# AUDIO.net
KiCad netlist of a schematic drawn in Altium Designer
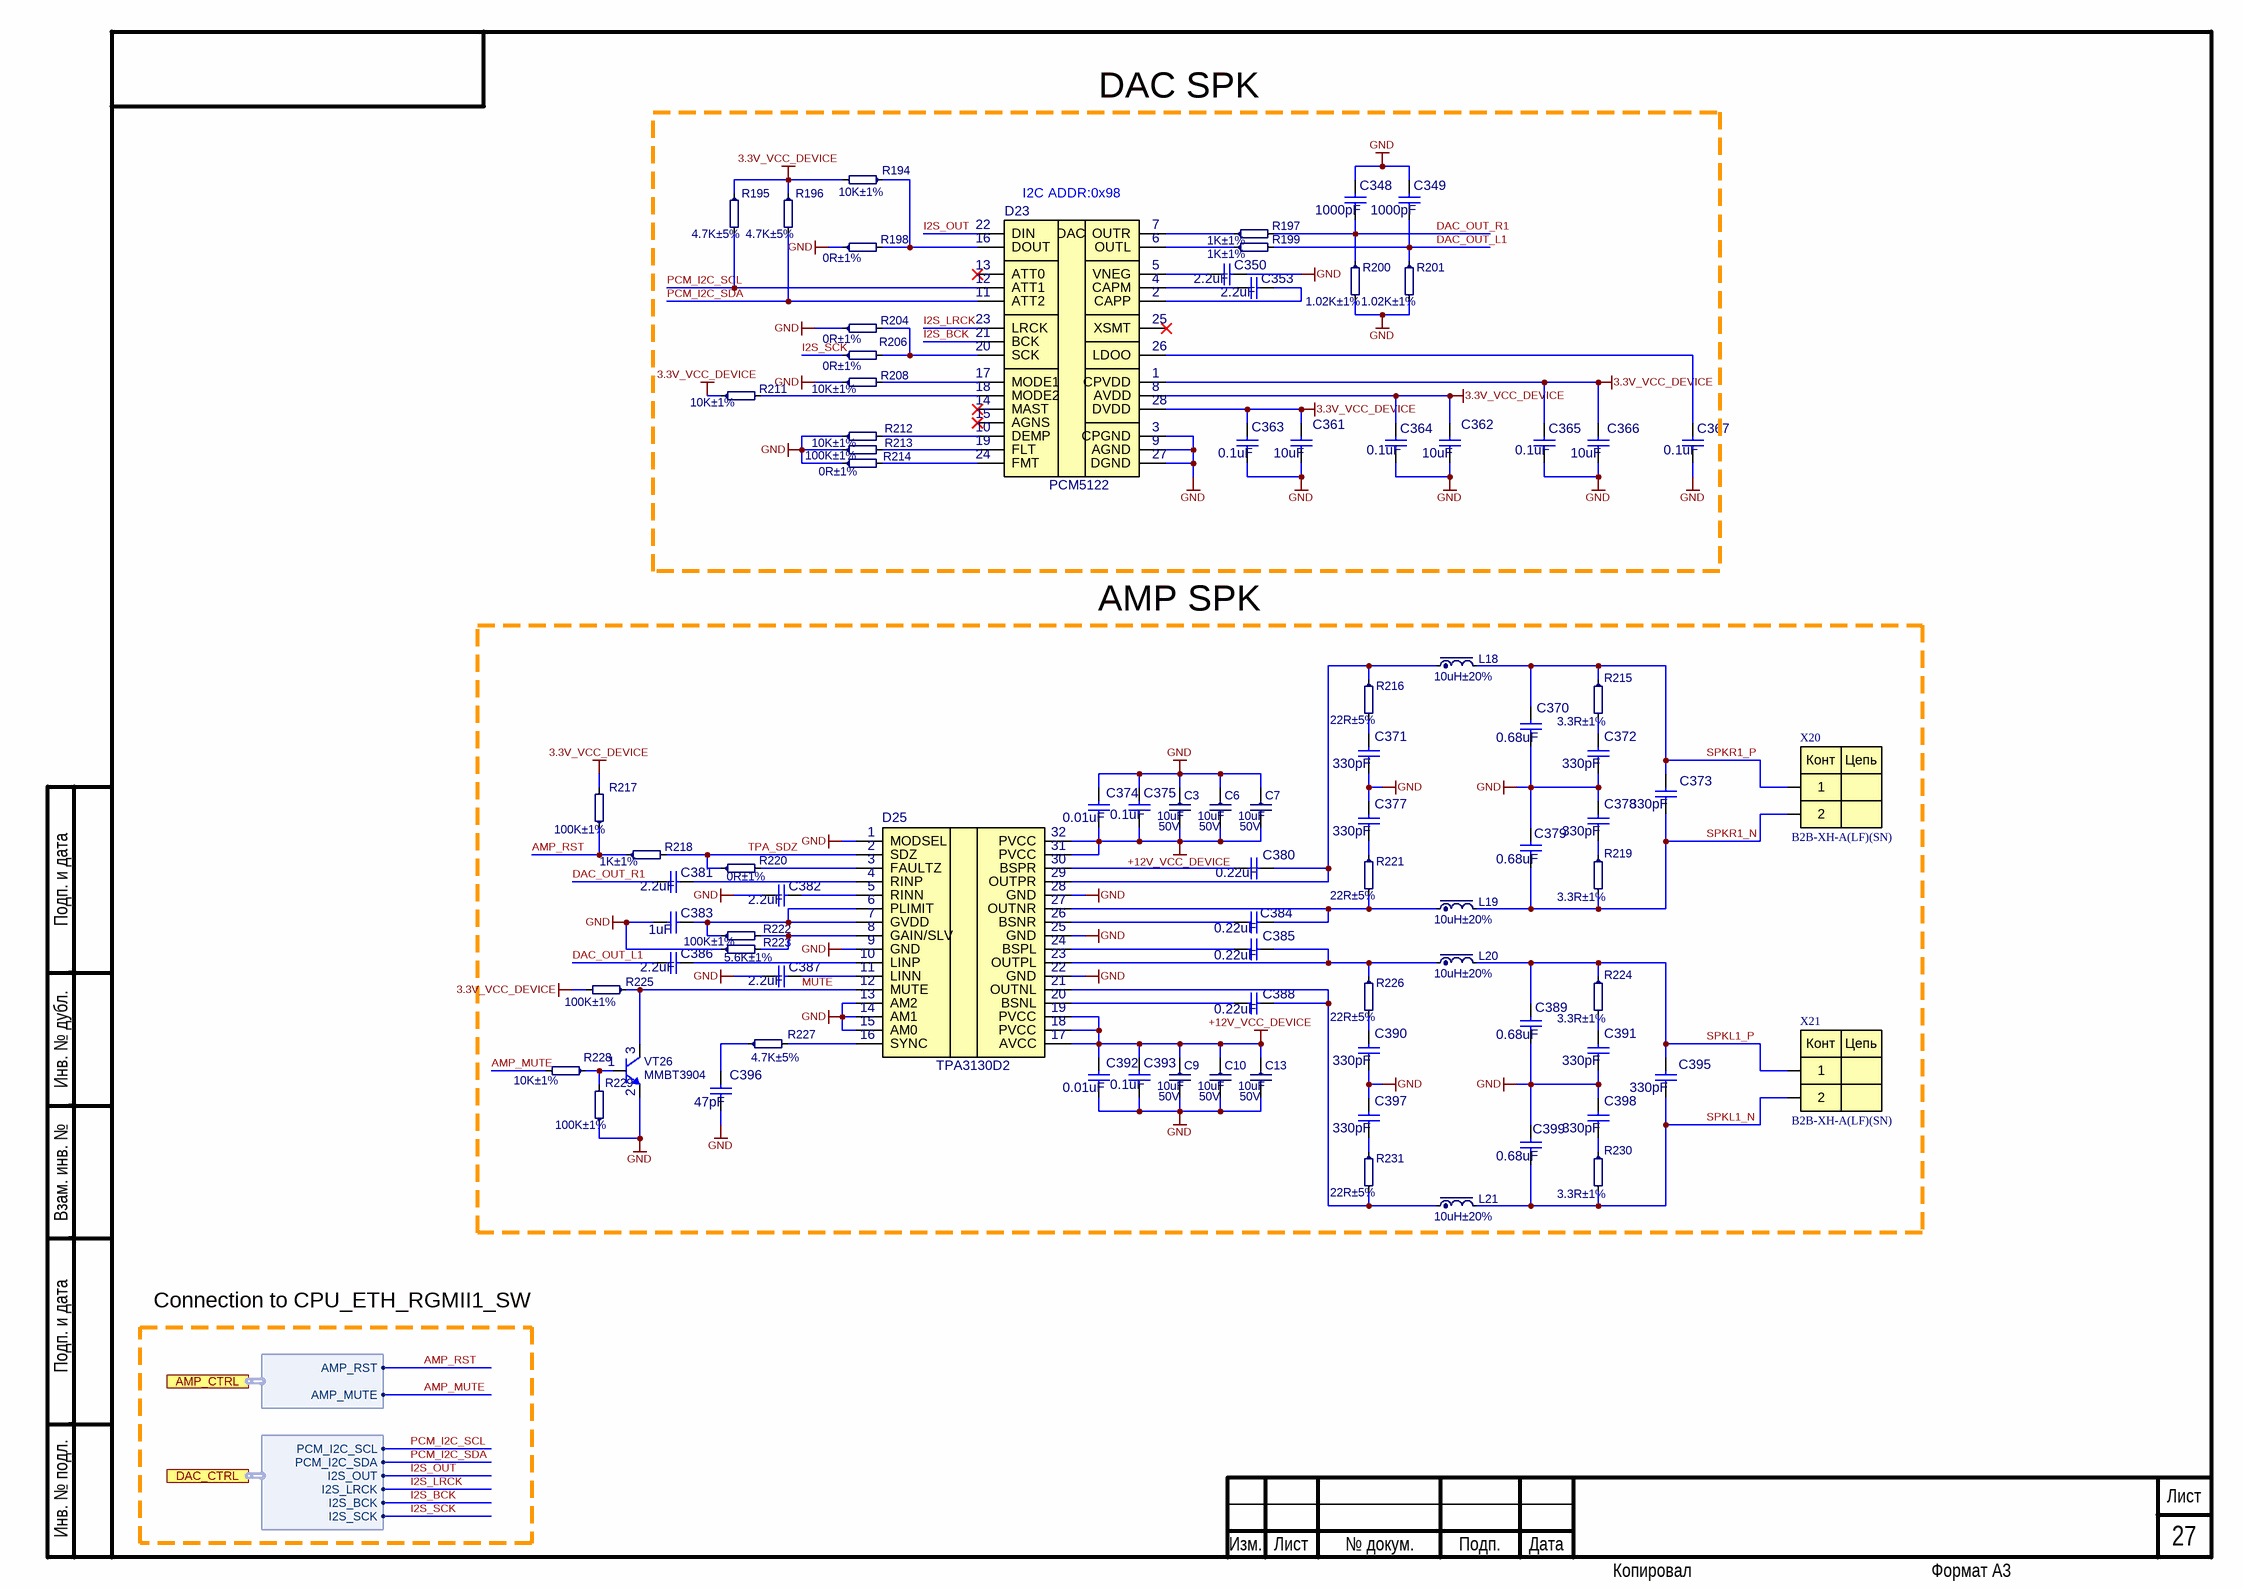
[diagram p0: AUDIO.SchDoc]

(export (version "E")
  (design (tool "Eeschema 10.0.6"))
  (components
    (comp (ref "C3")
      (value "10uF")
      (footprint "C1206")
      (fields
        (field (name "VOLTAGE") "50V")
        (field (name "PART NUMBER") "1206-X5R-50V-010uF±10%")
        (field (name "TOLERANCE") "10%")
        (field (name "MANUFACTURER") "Yageo")
      )
      (libsource (lib "") (part "C_1"))
    )
    (comp (ref "C6")
      (value "10uF")
      (footprint "C1206")
      (fields
        (field (name "VOLTAGE") "50V")
        (field (name "PART NUMBER") "1206-X5R-50V-010uF±10%")
        (field (name "TOLERANCE") "10%")
        (field (name "MANUFACTURER") "Yageo")
      )
      (libsource (lib "") (part "C_1"))
    )
    (comp (ref "C7")
      (value "10uF")
      (footprint "C1206")
      (fields
        (field (name "VOLTAGE") "50V")
        (field (name "PART NUMBER") "1206-X5R-50V-010uF±10%")
        (field (name "TOLERANCE") "10%")
        (field (name "MANUFACTURER") "Yageo")
      )
      (libsource (lib "") (part "C_1"))
    )
    (comp (ref "C9")
      (value "10uF")
      (footprint "C1206")
      (fields
        (field (name "VOLTAGE") "50V")
        (field (name "PART NUMBER") "1206-X5R-50V-010uF±10%")
        (field (name "TOLERANCE") "10%")
        (field (name "MANUFACTURER") "Yageo")
      )
      (libsource (lib "") (part "C_1"))
    )
    (comp (ref "C10")
      (value "10uF")
      (footprint "C1206")
      (fields
        (field (name "VOLTAGE") "50V")
        (field (name "PART NUMBER") "1206-X5R-50V-010uF±10%")
        (field (name "TOLERANCE") "10%")
        (field (name "MANUFACTURER") "Yageo")
      )
      (libsource (lib "") (part "C_1"))
    )
    (comp (ref "C13")
      (value "10uF")
      (footprint "C1206")
      (fields
        (field (name "VOLTAGE") "50V")
        (field (name "PART NUMBER") "1206-X5R-50V-010uF±10%")
        (field (name "TOLERANCE") "10%")
        (field (name "MANUFACTURER") "Yageo")
      )
      (libsource (lib "") (part "C_1"))
    )
    (comp (ref "C348")
      (value "1000pF")
      (footprint "C0402")
      (fields
        (field (name "PART NUMBER") "0402-X7R-50V-1000pF±5%")
        (field (name "VOLTAGE") "50V")
        (field (name "TOLERANCE") "5%")
      )
      (libsource (lib "ATB") (part "C"))
    )
    (comp (ref "C349")
      (value "1000pF")
      (footprint "C0402")
      (fields
        (field (name "PART NUMBER") "0402-X7R-50V-1000pF±5%")
        (field (name "VOLTAGE") "50V")
        (field (name "TOLERANCE") "5%")
      )
      (libsource (lib "ATB") (part "C"))
    )
    (comp (ref "C350")
      (value "2.2uF")
      (footprint "C0402")
      (fields
        (field (name "PART NUMBER") "0402-X5R-16V-2.2uF±10%")
        (field (name "VOLTAGE") "16V")
        (field (name "TOLERANCE") "10%")
      )
      (libsource (lib "ATB") (part "C"))
    )
    (comp (ref "C353")
      (value "2.2uF")
      (footprint "C0402")
      (fields
        (field (name "PART NUMBER") "0402-X5R-16V-2.2uF±10%")
        (field (name "VOLTAGE") "16V")
        (field (name "TOLERANCE") "10%")
      )
      (libsource (lib "ATB") (part "C"))
    )
    (comp (ref "C361")
      (value "10uF")
      (footprint "C0603")
      (fields
        (field (name "PART NUMBER") "0603-X5R-10V-10uF±20%")
        (field (name "VOLTAGE") "10V")
        (field (name "TOLERANCE") "20%")
      )
      (libsource (lib "ATB") (part "C"))
    )
    (comp (ref "C362")
      (value "10uF")
      (footprint "C0603")
      (fields
        (field (name "PART NUMBER") "0603-X5R-10V-10uF±20%")
        (field (name "VOLTAGE") "10V")
        (field (name "TOLERANCE") "20%")
      )
      (libsource (lib "ATB") (part "C"))
    )
    (comp (ref "C363")
      (value "0.1uF")
      (footprint "C0402")
      (fields
        (field (name "PART NUMBER") "0402-X5R-50V-0.1uF±10%")
        (field (name "VOLTAGE") "50V")
        (field (name "TOLERANCE") "10%")
      )
      (libsource (lib "ATB") (part "C"))
    )
    (comp (ref "C364")
      (value "0.1uF")
      (footprint "C0402")
      (fields
        (field (name "PART NUMBER") "0402-X5R-50V-0.1uF±10%")
        (field (name "VOLTAGE") "50V")
        (field (name "TOLERANCE") "10%")
      )
      (libsource (lib "ATB") (part "C"))
    )
    (comp (ref "C365")
      (value "0.1uF")
      (footprint "C0402")
      (fields
        (field (name "PART NUMBER") "0402-X5R-50V-0.1uF±10%")
        (field (name "VOLTAGE") "50V")
        (field (name "TOLERANCE") "10%")
      )
      (libsource (lib "ATB") (part "C"))
    )
    (comp (ref "C366")
      (value "10uF")
      (footprint "C0603")
      (fields
        (field (name "PART NUMBER") "0603-X5R-10V-10uF±20%")
        (field (name "VOLTAGE") "10V")
        (field (name "TOLERANCE") "20%")
      )
      (libsource (lib "ATB") (part "C"))
    )
    (comp (ref "C367")
      (value "0.1uF")
      (footprint "C0402")
      (fields
        (field (name "PART NUMBER") "0402-X5R-50V-0.1uF±10%")
        (field (name "VOLTAGE") "50V")
        (field (name "TOLERANCE") "10%")
      )
      (libsource (lib "ATB") (part "C"))
    )
    (comp (ref "C370")
      (value "0.68uF")
      (footprint "C0603")
      (fields
        (field (name "PART NUMBER") "0603-X7R-25V-0.68uF±10%")
        (field (name "VOLTAGE") "25V")
        (field (name "TOLERANCE") "10%")
      )
      (libsource (lib "ATB") (part "C"))
    )
    (comp (ref "C371")
      (value "330pF")
      (footprint "C0603")
      (fields
        (field (name "PART NUMBER") "0603-NP0-50V-330pF±5%")
        (field (name "VOLTAGE") "50V")
        (field (name "TOLERANCE") "5%")
      )
      (libsource (lib "ATB") (part "C"))
    )
    (comp (ref "C372")
      (value "330pF")
      (footprint "C0603")
      (fields
        (field (name "PART NUMBER") "0603-NP0-50V-330pF±5%")
        (field (name "VOLTAGE") "50V")
        (field (name "TOLERANCE") "5%")
      )
      (libsource (lib "ATB") (part "C"))
    )
    (comp (ref "C373")
      (value "330pF")
      (footprint "C0603")
      (fields
        (field (name "PART NUMBER") "0603-NP0-50V-330pF±5%")
        (field (name "VOLTAGE") "50V")
        (field (name "TOLERANCE") "5%")
      )
      (libsource (lib "ATB") (part "C"))
    )
    (comp (ref "C374")
      (value "0.01uF")
      (footprint "C0402")
      (fields
        (field (name "PART NUMBER") "0402-X7R-50V-0.01uF±10%")
        (field (name "VOLTAGE") "50V")
        (field (name "TOLERANCE") "10%")
      )
      (libsource (lib "ATB") (part "C"))
    )
    (comp (ref "C375")
      (value "0.1uF")
      (footprint "C0402")
      (fields
        (field (name "PART NUMBER") "0402-X5R-50V-0.1uF±10%")
        (field (name "VOLTAGE") "50V")
        (field (name "TOLERANCE") "10%")
      )
      (libsource (lib "ATB") (part "C"))
    )
    (comp (ref "C377")
      (value "330pF")
      (footprint "C0603")
      (fields
        (field (name "PART NUMBER") "0603-NP0-50V-330pF±5%")
        (field (name "VOLTAGE") "50V")
        (field (name "TOLERANCE") "5%")
      )
      (libsource (lib "ATB") (part "C"))
    )
    (comp (ref "C378")
      (value "330pF")
      (footprint "C0603")
      (fields
        (field (name "PART NUMBER") "0603-NP0-50V-330pF±5%")
        (field (name "VOLTAGE") "50V")
        (field (name "TOLERANCE") "5%")
      )
      (libsource (lib "ATB") (part "C"))
    )
    (comp (ref "C379")
      (value "0.68uF")
      (footprint "C0603")
      (fields
        (field (name "PART NUMBER") "0603-X7R-25V-0.68uF±10%")
        (field (name "VOLTAGE") "25V")
        (field (name "TOLERANCE") "10%")
      )
      (libsource (lib "ATB") (part "C"))
    )
    (comp (ref "C380")
      (value "0.22uF")
      (footprint "C0603")
      (fields
        (field (name "PART NUMBER") "0603-X5R-50V-0.22uF±10%")
        (field (name "VOLTAGE") "50V")
        (field (name "TOLERANCE") "10%")
      )
      (libsource (lib "ATB") (part "C"))
    )
    (comp (ref "C381")
      (value "2.2uF")
      (footprint "C0402")
      (fields
        (field (name "PART NUMBER") "0402-X5R-16V-2.2uF±10%")
        (field (name "VOLTAGE") "16V")
        (field (name "TOLERANCE") "10%")
      )
      (libsource (lib "ATB") (part "C"))
    )
    (comp (ref "C382")
      (value "2.2uF")
      (footprint "C0402")
      (fields
        (field (name "PART NUMBER") "0402-X5R-16V-2.2uF±10%")
        (field (name "VOLTAGE") "16V")
        (field (name "TOLERANCE") "10%")
      )
      (libsource (lib "ATB") (part "C"))
    )
    (comp (ref "C383")
      (value "1uF")
      (footprint "C0402")
      (fields
        (field (name "PART NUMBER") "0402-X5R-10V-1uF±10%")
        (field (name "VOLTAGE") "10V")
        (field (name "TOLERANCE") "10%")
      )
      (libsource (lib "ATB") (part "C"))
    )
    (comp (ref "C384")
      (value "0.22uF")
      (footprint "C0603")
      (fields
        (field (name "PART NUMBER") "0603-X5R-50V-0.22uF±10%")
        (field (name "VOLTAGE") "50V")
        (field (name "TOLERANCE") "10%")
      )
      (libsource (lib "ATB") (part "C"))
    )
    (comp (ref "C385")
      (value "0.22uF")
      (footprint "C0603")
      (fields
        (field (name "PART NUMBER") "0603-X5R-50V-0.22uF±10%")
        (field (name "VOLTAGE") "50V")
        (field (name "TOLERANCE") "10%")
      )
      (libsource (lib "ATB") (part "C"))
    )
    (comp (ref "C386")
      (value "2.2uF")
      (footprint "C0402")
      (fields
        (field (name "PART NUMBER") "0402-X5R-16V-2.2uF±10%")
        (field (name "VOLTAGE") "16V")
        (field (name "TOLERANCE") "10%")
      )
      (libsource (lib "ATB") (part "C"))
    )
    (comp (ref "C387")
      (value "2.2uF")
      (footprint "C0402")
      (fields
        (field (name "PART NUMBER") "0402-X5R-16V-2.2uF±10%")
        (field (name "VOLTAGE") "16V")
        (field (name "TOLERANCE") "10%")
      )
      (libsource (lib "ATB") (part "C"))
    )
    (comp (ref "C388")
      (value "0.22uF")
      (footprint "C0603")
      (fields
        (field (name "PART NUMBER") "0603-X5R-50V-0.22uF±10%")
        (field (name "VOLTAGE") "50V")
        (field (name "TOLERANCE") "10%")
      )
      (libsource (lib "ATB") (part "C"))
    )
    (comp (ref "C389")
      (value "0.68uF")
      (footprint "C0603")
      (fields
        (field (name "PART NUMBER") "0603-X7R-25V-0.68uF±10%")
        (field (name "VOLTAGE") "25V")
        (field (name "TOLERANCE") "10%")
      )
      (libsource (lib "ATB") (part "C"))
    )
    (comp (ref "C390")
      (value "330pF")
      (footprint "C0603")
      (fields
        (field (name "PART NUMBER") "0603-NP0-50V-330pF±5%")
        (field (name "VOLTAGE") "50V")
        (field (name "TOLERANCE") "5%")
      )
      (libsource (lib "ATB") (part "C"))
    )
    (comp (ref "C391")
      (value "330pF")
      (footprint "C0603")
      (fields
        (field (name "PART NUMBER") "0603-NP0-50V-330pF±5%")
        (field (name "VOLTAGE") "50V")
        (field (name "TOLERANCE") "5%")
      )
      (libsource (lib "ATB") (part "C"))
    )
    (comp (ref "C392")
      (value "0.01uF")
      (footprint "C0402")
      (fields
        (field (name "PART NUMBER") "0402-X7R-50V-0.01uF±10%")
        (field (name "VOLTAGE") "50V")
        (field (name "TOLERANCE") "10%")
      )
      (libsource (lib "ATB") (part "C"))
    )
    (comp (ref "C393")
      (value "0.1uF")
      (footprint "C0402")
      (fields
        (field (name "PART NUMBER") "0402-X5R-50V-0.1uF±10%")
        (field (name "VOLTAGE") "50V")
        (field (name "TOLERANCE") "10%")
      )
      (libsource (lib "ATB") (part "C"))
    )
    (comp (ref "C395")
      (value "330pF")
      (footprint "C0603")
      (fields
        (field (name "PART NUMBER") "0603-NP0-50V-330pF±5%")
        (field (name "VOLTAGE") "50V")
        (field (name "TOLERANCE") "5%")
      )
      (libsource (lib "ATB") (part "C"))
    )
    (comp (ref "C396")
      (value "47pF")
      (footprint "C0402")
      (fields
        (field (name "PART NUMBER") "0402-NP0-50V-047pF±5%")
        (field (name "VOLTAGE") "50V")
        (field (name "TOLERANCE") "5%")
      )
      (libsource (lib "ATB") (part "C"))
    )
    (comp (ref "C397")
      (value "330pF")
      (footprint "C0603")
      (fields
        (field (name "PART NUMBER") "0603-NP0-50V-330pF±5%")
        (field (name "VOLTAGE") "50V")
        (field (name "TOLERANCE") "5%")
      )
      (libsource (lib "ATB") (part "C"))
    )
    (comp (ref "C398")
      (value "330pF")
      (footprint "C0603")
      (fields
        (field (name "PART NUMBER") "0603-NP0-50V-330pF±5%")
        (field (name "VOLTAGE") "50V")
        (field (name "TOLERANCE") "5%")
      )
      (libsource (lib "ATB") (part "C"))
    )
    (comp (ref "C399")
      (value "0.68uF")
      (footprint "C0603")
      (fields
        (field (name "PART NUMBER") "0603-X7R-25V-0.68uF±10%")
        (field (name "VOLTAGE") "25V")
        (field (name "TOLERANCE") "10%")
      )
      (libsource (lib "ATB") (part "C"))
    )
    (comp (ref "D23")
      (value "PCM5122")
      (footprint "TSSOP65-28")
      (description "2V RMS DIRECTPATH 106dB Audio Stereo DAC with PCM interface and fixed Audio processing")
      (fields (field (name "MANUFACTURER") "Texas Instruments"))
      (libsource (lib "ATB") (part "PCM5121_HM"))
    )
    (comp (ref "D25")
      (value "TPA3130D2")
      (footprint "TSOP65P810X115-32M")
      (description "TPA3130D2 Evaluation Module")
      (fields (field (name "MANUFACTURER") "Texas Instruments"))
      (libsource (lib "ATB") (part "TPA3116D2"))
    )
    (comp (ref "L18")
      (value "10uH±20%")
      (footprint "MWSA0605S")
      (description "4.4A 10uH ±20% 4.5A SMD 7x6.6mm Power Inductor")
      (fields (field (name "PART NUMBER") "MWSA0605S-100MT") (field (name "TOLERANCE") "20%"))
      (libsource (lib "ATB") (part "L"))
    )
    (comp (ref "L19")
      (value "10uH±20%")
      (footprint "MWSA0605S")
      (description "4.4A 10uH ±20% 4.5A SMD 7x6.6mm Power Inductor")
      (fields (field (name "PART NUMBER") "MWSA0605S-100MT") (field (name "TOLERANCE") "20%"))
      (libsource (lib "ATB") (part "L"))
    )
    (comp (ref "L20")
      (value "10uH±20%")
      (footprint "MWSA0605S")
      (description "4.4A 10uH ±20% 4.5A SMD 7x6.6mm Power Inductor")
      (fields (field (name "PART NUMBER") "MWSA0605S-100MT") (field (name "TOLERANCE") "20%"))
      (libsource (lib "ATB") (part "L"))
    )
    (comp (ref "L21")
      (value "10uH±20%")
      (footprint "MWSA0605S")
      (description "4.4A 10uH ±20% 4.5A SMD 7x6.6mm Power Inductor")
      (fields (field (name "PART NUMBER") "MWSA0605S-100MT") (field (name "TOLERANCE") "20%"))
      (libsource (lib "ATB") (part "L"))
    )
    (comp (ref "R194")
      (value "10K±1%")
      (footprint "R0402")
      (description "Chip Resistor 0402 10kΩ ±1% 50V ±100ppm/℃ Thick Film")
      (fields (field (name "PART NUMBER") "0402-0.0625W-10K-100ppm±1%") (field (name "TOLERANCE") "1%"))
      (libsource (lib "ATB") (part "R"))
    )
    (comp (ref "R195")
      (value "4.7K±5%")
      (footprint "R0402")
      (fields
        (field (name "PART NUMBER") "0402-0.0625W-4.7K-100ppm±5%")
        (field (name "TOLERANCE") "5%")
        (field (name "MANUFACTURER") "Yageo")
      )
      (libsource (lib "ATB") (part "R"))
    )
    (comp (ref "R196")
      (value "4.7K±5%")
      (footprint "R0402")
      (fields
        (field (name "PART NUMBER") "0402-0.0625W-4.7K-100ppm±5%")
        (field (name "TOLERANCE") "5%")
        (field (name "MANUFACTURER") "Yageo")
      )
      (libsource (lib "ATB") (part "R"))
    )
    (comp (ref "R197")
      (value "1K±1%")
      (footprint "R0402")
      (fields
        (field (name "PART NUMBER") "0402-0.0625W-1K-100ppm±1%")
        (field (name "TOLERANCE") "1%")
        (field (name "MANUFACTURER") "Yageo")
      )
      (libsource (lib "ATB") (part "R"))
    )
    (comp (ref "R198")
      (value "0R±1%")
      (footprint "R0402")
      (description "Chip Resistor 0402 0Ω ±1% 50V ±100ppm/℃ Thick Film")
      (fields (field (name "PART NUMBER") "0402-0.0625W-0R-100ppm±1%") (field (name "TOLERANCE") "1%"))
      (libsource (lib "ATB") (part "R"))
    )
    (comp (ref "R199")
      (value "1K±1%")
      (footprint "R0402")
      (fields
        (field (name "PART NUMBER") "0402-0.0625W-1K-100ppm±1%")
        (field (name "TOLERANCE") "1%")
        (field (name "MANUFACTURER") "Yageo")
      )
      (libsource (lib "ATB") (part "R"))
    )
    (comp (ref "R200")
      (value "1.02K±1%")
      (footprint "R0402")
      (fields
        (field (name "PART NUMBER") "0402-0.0625W-1.02K-100ppm±1%")
        (field (name "TOLERANCE") "1%")
        (field (name "MANUFACTURER") "Yageo")
      )
      (libsource (lib "ATB") (part "R"))
    )
    (comp (ref "R201")
      (value "1.02K±1%")
      (footprint "R0402")
      (fields
        (field (name "PART NUMBER") "0402-0.0625W-1.02K-100ppm±1%")
        (field (name "TOLERANCE") "1%")
        (field (name "MANUFACTURER") "Yageo")
      )
      (libsource (lib "ATB") (part "R"))
    )
    (comp (ref "R204")
      (value "0R±1%")
      (footprint "R0402")
      (description "Chip Resistor 0402 0Ω ±1% 50V ±100ppm/℃ Thick Film")
      (fields (field (name "PART NUMBER") "0402-0.0625W-0R-100ppm±1%") (field (name "TOLERANCE") "1%"))
      (libsource (lib "ATB") (part "R"))
    )
    (comp (ref "R206")
      (value "0R±1%")
      (footprint "R0402")
      (description "Chip Resistor 0402 0Ω ±1% 50V ±100ppm/℃ Thick Film")
      (fields (field (name "PART NUMBER") "0402-0.0625W-0R-100ppm±1%") (field (name "TOLERANCE") "1%"))
      (libsource (lib "ATB") (part "R"))
    )
    (comp (ref "R208")
      (value "10K±1%")
      (footprint "R0402")
      (description "Chip Resistor 0402 10kΩ ±1% 50V ±100ppm/℃ Thick Film")
      (fields (field (name "PART NUMBER") "0402-0.0625W-10K-100ppm±1%") (field (name "TOLERANCE") "1%"))
      (libsource (lib "ATB") (part "R"))
    )
    (comp (ref "R211")
      (value "10K±1%")
      (footprint "R0402")
      (description "Chip Resistor 0402 10kΩ ±1% 50V ±100ppm/℃ Thick Film")
      (fields (field (name "PART NUMBER") "0402-0.0625W-10K-100ppm±1%") (field (name "TOLERANCE") "1%"))
      (libsource (lib "ATB") (part "R"))
    )
    (comp (ref "R212")
      (value "10K±1%")
      (footprint "R0402")
      (description "Chip Resistor 0402 10kΩ ±1% 50V ±100ppm/℃ Thick Film")
      (fields (field (name "PART NUMBER") "0402-0.0625W-10K-100ppm±1%") (field (name "TOLERANCE") "1%"))
      (libsource (lib "ATB") (part "R"))
    )
    (comp (ref "R213")
      (value "100K±1%")
      (footprint "R0402")
      (description "Chip Resistor 0402 100kΩ ±1% 50V ±100ppm/℃ Thick Film")
      (fields (field (name "PART NUMBER") "0402-0.0625W-100K-100ppm±1%") (field (name "TOLERANCE") "1%"))
      (libsource (lib "ATB") (part "R"))
    )
    (comp (ref "R214")
      (value "0R±1%")
      (footprint "R0402")
      (description "Chip Resistor 0402 0Ω ±1% 50V ±100ppm/℃ Thick Film")
      (fields (field (name "PART NUMBER") "0402-0.0625W-0R-100ppm±1%") (field (name "TOLERANCE") "1%"))
      (libsource (lib "ATB") (part "R"))
    )
    (comp (ref "R215")
      (value "3.3R±1%")
      (footprint "R0603")
      (fields
        (field (name "PART NUMBER") "0603-0.1W-3.3R-200ppm±1%")
        (field (name "TOLERANCE") "1%")
        (field (name "MANUFACTURER") "Yageo")
      )
      (libsource (lib "ATB") (part "R"))
    )
    (comp (ref "R216")
      (value "22R±5%")
      (footprint "R0603")
      (fields
        (field (name "PART NUMBER") "0603-0.1W-22R-100ppm±5%")
        (field (name "TOLERANCE") "5%")
        (field (name "MANUFACTURER") "Yageo")
      )
      (libsource (lib "ATB") (part "R"))
    )
    (comp (ref "R217")
      (value "100K±1%")
      (footprint "R0402")
      (description "Chip Resistor 0402 100kΩ ±1% 50V ±100ppm/℃ Thick Film")
      (fields (field (name "PART NUMBER") "0402-0.0625W-100K-100ppm±1%") (field (name "TOLERANCE") "1%"))
      (libsource (lib "ATB") (part "R"))
    )
    (comp (ref "R218")
      (value "1K±1%")
      (footprint "R0402")
      (fields
        (field (name "PART NUMBER") "0402-0.0625W-1K-100ppm±1%")
        (field (name "TOLERANCE") "1%")
        (field (name "MANUFACTURER") "Yageo")
      )
      (libsource (lib "ATB") (part "R"))
    )
    (comp (ref "R219")
      (value "3.3R±1%")
      (footprint "R0603")
      (fields
        (field (name "PART NUMBER") "0603-0.1W-3.3R-200ppm±1%")
        (field (name "TOLERANCE") "1%")
        (field (name "MANUFACTURER") "Yageo")
      )
      (libsource (lib "ATB") (part "R"))
    )
    (comp (ref "R220")
      (value "0R±1%")
      (footprint "R0402")
      (description "Chip Resistor 0402 0Ω ±1% 50V ±100ppm/℃ Thick Film")
      (fields (field (name "PART NUMBER") "0402-0.0625W-0R-100ppm±1%") (field (name "TOLERANCE") "1%"))
      (libsource (lib "ATB") (part "R"))
    )
    (comp (ref "R221")
      (value "22R±5%")
      (footprint "R0603")
      (fields
        (field (name "PART NUMBER") "0603-0.1W-22R-100ppm±5%")
        (field (name "TOLERANCE") "5%")
        (field (name "MANUFACTURER") "Yageo")
      )
      (libsource (lib "ATB") (part "R"))
    )
    (comp (ref "R222")
      (value "100K±1%")
      (footprint "R0402")
      (description "Chip Resistor 0402 100kΩ ±1% 50V ±100ppm/℃ Thick Film")
      (fields (field (name "PART NUMBER") "0402-0.0625W-100K-100ppm±1%") (field (name "TOLERANCE") "1%"))
      (libsource (lib "ATB") (part "R"))
    )
    (comp (ref "R223")
      (value "5.6K±1%")
      (footprint "R0402")
      (fields
        (field (name "PART NUMBER") "0402-0.0625W-5.6K-100ppm±1%")
        (field (name "TOLERANCE") "1%")
        (field (name "MANUFACTURER") "Yageo")
      )
      (libsource (lib "ATB") (part "R"))
    )
    (comp (ref "R224")
      (value "3.3R±1%")
      (footprint "R0603")
      (fields
        (field (name "PART NUMBER") "0603-0.1W-3.3R-200ppm±1%")
        (field (name "TOLERANCE") "1%")
        (field (name "MANUFACTURER") "Yageo")
      )
      (libsource (lib "ATB") (part "R"))
    )
    (comp (ref "R225")
      (value "100K±1%")
      (footprint "R0402")
      (description "Chip Resistor 0402 100kΩ ±1% 50V ±100ppm/℃ Thick Film")
      (fields (field (name "PART NUMBER") "0402-0.0625W-100K-100ppm±1%") (field (name "TOLERANCE") "1%"))
      (libsource (lib "ATB") (part "R"))
    )
    (comp (ref "R226")
      (value "22R±5%")
      (footprint "R0603")
      (fields
        (field (name "PART NUMBER") "0603-0.1W-22R-100ppm±5%")
        (field (name "TOLERANCE") "5%")
        (field (name "MANUFACTURER") "Yageo")
      )
      (libsource (lib "ATB") (part "R"))
    )
    (comp (ref "R227")
      (value "4.7K±5%")
      (footprint "R0402")
      (fields
        (field (name "PART NUMBER") "0402-0.0625W-4.7K-100ppm±5%")
        (field (name "TOLERANCE") "5%")
        (field (name "MANUFACTURER") "Yageo")
      )
      (libsource (lib "ATB") (part "R"))
    )
    (comp (ref "R228")
      (value "10K±1%")
      (footprint "R0402")
      (description "Chip Resistor 0402 10kΩ ±1% 50V ±100ppm/℃ Thick Film")
      (fields (field (name "PART NUMBER") "0402-0.0625W-10K-100ppm±1%") (field (name "TOLERANCE") "1%"))
      (libsource (lib "ATB") (part "R"))
    )
    (comp (ref "R229")
      (value "100K±1%")
      (footprint "R0402")
      (description "Chip Resistor 0402 100kΩ ±1% 50V ±100ppm/℃ Thick Film")
      (fields (field (name "PART NUMBER") "0402-0.0625W-100K-100ppm±1%") (field (name "TOLERANCE") "1%"))
      (libsource (lib "ATB") (part "R"))
    )
    (comp (ref "R230")
      (value "3.3R±1%")
      (footprint "R0603")
      (fields
        (field (name "PART NUMBER") "0603-0.1W-3.3R-200ppm±1%")
        (field (name "TOLERANCE") "1%")
        (field (name "MANUFACTURER") "Yageo")
      )
      (libsource (lib "ATB") (part "R"))
    )
    (comp (ref "R231")
      (value "22R±5%")
      (footprint "R0603")
      (fields
        (field (name "PART NUMBER") "0603-0.1W-22R-100ppm±5%")
        (field (name "TOLERANCE") "5%")
        (field (name "MANUFACTURER") "Yageo")
      )
      (libsource (lib "ATB") (part "R"))
    )
    (comp (ref "VT26")
      (value "MMBT3904")
      (footprint "SOT23")
      (description "NPN transistor")
      (fields (field (name "VOLTAGE") "40V") (field (name "MANUFACTURER") "Diotec Semiconductor"))
      (libsource (lib "ATB") (part "BC846BLT1G"))
    )
    (comp (ref "X20")
      (value "B2B-XH-A(LF)(SN)")
      (footprint "B2B-XH-A(LF)(SN)")
      (description "Connector Header 2 position 2.5mm Pitch 3A Through Hole -25℃~+85℃")
      (fields (field (name "MANUFACTURER") "JST"))
      (libsource (lib "LIB_RK") (part "B2B-XH-A(LF)(SN)"))
    )
    (comp (ref "X21")
      (value "B2B-XH-A(LF)(SN)")
      (footprint "B2B-XH-A(LF)(SN)")
      (description "Connector Header 2 position 2.5mm Pitch 3A Through Hole -25℃~+85℃")
      (fields (field (name "MANUFACTURER") "JST"))
      (libsource (lib "LIB_RK") (part "B2B-XH-A(LF)(SN)"))
    )
  )
  (nets
    (net (code "3") (name "+12V_VCC_DEVICE") (class "Default")
      (node (ref "C10") (pin "1") (pinfunction "1_1") (pintype "passive"))
      (node (ref "C13") (pin "1") (pinfunction "1_1") (pintype "passive"))
      (node (ref "C3") (pin "2") (pinfunction "2_2") (pintype "passive"))
      (node (ref "C374") (pin "1") (pinfunction "1_1") (pintype "passive"))
      (node (ref "C375") (pin "1") (pinfunction "1_1") (pintype "passive"))
      (node (ref "C392") (pin "2") (pinfunction "2_2") (pintype "passive"))
      (node (ref "C393") (pin "2") (pinfunction "2_2") (pintype "passive"))
      (node (ref "C6") (pin "2") (pinfunction "2_2") (pintype "passive"))
      (node (ref "C7") (pin "2") (pinfunction "2_2") (pintype "passive"))
      (node (ref "C9") (pin "1") (pinfunction "1_1") (pintype "passive"))
      (node (ref "D25") (pin "17") (pinfunction "AVCC_17") (pintype "passive"))
      (node (ref "D25") (pin "18") (pinfunction "PVCC_18") (pintype "passive"))
      (node (ref "D25") (pin "19") (pinfunction "PVCC_19") (pintype "passive"))
      (node (ref "D25") (pin "31") (pinfunction "PVCC_31") (pintype "passive"))
      (node (ref "D25") (pin "32") (pinfunction "PVCC_32") (pintype "passive"))
    )
    (net (code "4") (name "/AMP_MUTE") (class "Default")
      (node (ref "R228") (pin "2") (pinfunction "2_2") (pintype "passive"))
    )
    (net (code "5") (name "/AMP_RST") (class "Default")
      (node (ref "R217") (pin "1") (pinfunction "1_1") (pintype "passive"))
      (node (ref "R218") (pin "1") (pinfunction "1_1") (pintype "passive"))
    )
    (net (code "6") (name "/DAC_OUT_L1") (class "Default")
      (node (ref "C349") (pin "2") (pinfunction "2_2") (pintype "passive"))
      (node (ref "C386") (pin "1") (pinfunction "1_1") (pintype "passive"))
      (node (ref "R199") (pin "2") (pinfunction "2_2") (pintype "passive"))
      (node (ref "R201") (pin "1") (pinfunction "1_1") (pintype "passive"))
    )
    (net (code "7") (name "/DAC_OUT_R1") (class "Default")
      (node (ref "C348") (pin "2") (pinfunction "2_2") (pintype "passive"))
      (node (ref "C381") (pin "1") (pinfunction "1_1") (pintype "passive"))
      (node (ref "R197") (pin "2") (pinfunction "2_2") (pintype "passive"))
      (node (ref "R200") (pin "1") (pinfunction "1_1") (pintype "passive"))
    )
    (net (code "8") (name "/I2S_BCK") (class "Default")
      (node (ref "D23") (pin "21") (pinfunction "BCK_21") (pintype "passive"))
    )
    (net (code "9") (name "/I2S_LRCK") (class "Default")
      (node (ref "D23") (pin "23") (pinfunction "LRCK_23") (pintype "passive"))
    )
    (net (code "10") (name "/I2S_OUT") (class "Default")
      (node (ref "D23") (pin "22") (pinfunction "DIN_22") (pintype "passive"))
    )
    (net (code "11") (name "/I2S_SCK") (class "Default")
      (node (ref "R206") (pin "1") (pinfunction "1_1") (pintype "passive"))
    )
    (net (code "12") (name "/MUTE") (class "Default")
      (node (ref "D25") (pin "12") (pinfunction "MUTE_12") (pintype "passive"))
      (node (ref "R225") (pin "1") (pinfunction "1_1") (pintype "passive"))
      (node (ref "VT26") (pin "3") (pinfunction "C_3") (pintype "passive"))
    )
    (net (code "13") (name "/PCM_I2C_SCL") (class "Default")
      (node (ref "D23") (pin "12") (pinfunction "ATT1_12") (pintype "passive"))
      (node (ref "R195") (pin "2") (pinfunction "2_2") (pintype "passive"))
    )
    (net (code "14") (name "/PCM_I2C_SDA") (class "Default")
      (node (ref "D23") (pin "11") (pinfunction "ATT2_11") (pintype "passive"))
      (node (ref "R196") (pin "2") (pinfunction "2_2") (pintype "passive"))
    )
    (net (code "15") (name "/SPKL1_N") (class "Default")
      (node (ref "C395") (pin "1") (pinfunction "1_1") (pintype "passive"))
      (node (ref "C399") (pin "1") (pinfunction "1_1") (pintype "passive"))
      (node (ref "L21") (pin "2") (pinfunction "2_2") (pintype "passive"))
      (node (ref "R230") (pin "2") (pinfunction "2_2") (pintype "passive"))
      (node (ref "X21") (pin "2") (pinfunction "2_2") (pintype "passive"))
    )
    (net (code "16") (name "/SPKL1_P") (class "Default")
      (node (ref "C389") (pin "2") (pinfunction "2_2") (pintype "passive"))
      (node (ref "C395") (pin "2") (pinfunction "2_2") (pintype "passive"))
      (node (ref "L20") (pin "2") (pinfunction "2_2") (pintype "passive"))
      (node (ref "R224") (pin "1") (pinfunction "1_1") (pintype "passive"))
      (node (ref "X21") (pin "1") (pinfunction "1_1") (pintype "passive"))
    )
    (net (code "17") (name "/SPKR1_N") (class "Default")
      (node (ref "C373") (pin "1") (pinfunction "1_1") (pintype "passive"))
      (node (ref "C379") (pin "1") (pinfunction "1_1") (pintype "passive"))
      (node (ref "L19") (pin "2") (pinfunction "2_2") (pintype "passive"))
      (node (ref "R219") (pin "2") (pinfunction "2_2") (pintype "passive"))
      (node (ref "X20") (pin "2") (pinfunction "2_2") (pintype "passive"))
    )
    (net (code "18") (name "/SPKR1_P") (class "Default")
      (node (ref "C370") (pin "2") (pinfunction "2_2") (pintype "passive"))
      (node (ref "C373") (pin "2") (pinfunction "2_2") (pintype "passive"))
      (node (ref "L18") (pin "2") (pinfunction "2_2") (pintype "passive"))
      (node (ref "R215") (pin "1") (pinfunction "1_1") (pintype "passive"))
      (node (ref "X20") (pin "1") (pinfunction "1_1") (pintype "passive"))
    )
    (net (code "19") (name "/TPA_SDZ") (class "Default")
      (node (ref "D25") (pin "2") (pinfunction "SDZ_2") (pintype "passive"))
      (node (ref "R218") (pin "2") (pinfunction "2_2") (pintype "passive"))
      (node (ref "R220") (pin "1") (pinfunction "1_1") (pintype "passive"))
    )
    (net (code "22") (name "3.3V_VCC_DEVICE") (class "Default")
      (node (ref "C361") (pin "2") (pinfunction "2_2") (pintype "passive"))
      (node (ref "C362") (pin "2") (pinfunction "2_2") (pintype "passive"))
      (node (ref "C363") (pin "2") (pinfunction "2_2") (pintype "passive"))
      (node (ref "C364") (pin "2") (pinfunction "2_2") (pintype "passive"))
      (node (ref "C365") (pin "2") (pinfunction "2_2") (pintype "passive"))
      (node (ref "C366") (pin "2") (pinfunction "2_2") (pintype "passive"))
      (node (ref "D23") (pin "1") (pinfunction "CPVDD_1") (pintype "passive"))
      (node (ref "D23") (pin "28") (pinfunction "DVDD_28") (pintype "passive"))
      (node (ref "D23") (pin "8") (pinfunction "AVDD_8") (pintype "passive"))
      (node (ref "R194") (pin "2") (pinfunction "2_2") (pintype "passive"))
      (node (ref "R195") (pin "1") (pinfunction "1_1") (pintype "passive"))
      (node (ref "R196") (pin "1") (pinfunction "1_1") (pintype "passive"))
      (node (ref "R211") (pin "1") (pinfunction "1_1") (pintype "passive"))
      (node (ref "R217") (pin "2") (pinfunction "2_2") (pintype "passive"))
      (node (ref "R225") (pin "2") (pinfunction "2_2") (pintype "passive"))
    )
    (net (code "23") (name "GND") (class "Default")
      (node (ref "C10") (pin "2") (pinfunction "2_2") (pintype "passive"))
      (node (ref "C13") (pin "2") (pinfunction "2_2") (pintype "passive"))
      (node (ref "C3") (pin "1") (pinfunction "1_1") (pintype "passive"))
      (node (ref "C348") (pin "1") (pinfunction "1_1") (pintype "passive"))
      (node (ref "C349") (pin "1") (pinfunction "1_1") (pintype "passive"))
      (node (ref "C350") (pin "2") (pinfunction "2_2") (pintype "passive"))
      (node (ref "C361") (pin "1") (pinfunction "1_1") (pintype "passive"))
      (node (ref "C362") (pin "1") (pinfunction "1_1") (pintype "passive"))
      (node (ref "C363") (pin "1") (pinfunction "1_1") (pintype "passive"))
      (node (ref "C364") (pin "1") (pinfunction "1_1") (pintype "passive"))
      (node (ref "C365") (pin "1") (pinfunction "1_1") (pintype "passive"))
      (node (ref "C366") (pin "1") (pinfunction "1_1") (pintype "passive"))
      (node (ref "C367") (pin "1") (pinfunction "1_1") (pintype "passive"))
      (node (ref "C370") (pin "1") (pinfunction "1_1") (pintype "passive"))
      (node (ref "C371") (pin "1") (pinfunction "1_1") (pintype "passive"))
      (node (ref "C372") (pin "1") (pinfunction "1_1") (pintype "passive"))
      (node (ref "C374") (pin "2") (pinfunction "2_2") (pintype "passive"))
      (node (ref "C375") (pin "2") (pinfunction "2_2") (pintype "passive"))
      (node (ref "C377") (pin "2") (pinfunction "2_2") (pintype "passive"))
      (node (ref "C378") (pin "2") (pinfunction "2_2") (pintype "passive"))
      (node (ref "C379") (pin "2") (pinfunction "2_2") (pintype "passive"))
      (node (ref "C382") (pin "1") (pinfunction "1_1") (pintype "passive"))
      (node (ref "C383") (pin "2") (pinfunction "2_2") (pintype "passive"))
      (node (ref "C387") (pin "1") (pinfunction "1_1") (pintype "passive"))
      (node (ref "C389") (pin "1") (pinfunction "1_1") (pintype "passive"))
      (node (ref "C390") (pin "1") (pinfunction "1_1") (pintype "passive"))
      (node (ref "C391") (pin "1") (pinfunction "1_1") (pintype "passive"))
      (node (ref "C392") (pin "1") (pinfunction "1_1") (pintype "passive"))
      (node (ref "C393") (pin "1") (pinfunction "1_1") (pintype "passive"))
      (node (ref "C396") (pin "1") (pinfunction "1_1") (pintype "passive"))
      (node (ref "C397") (pin "2") (pinfunction "2_2") (pintype "passive"))
      (node (ref "C398") (pin "2") (pinfunction "2_2") (pintype "passive"))
      (node (ref "C399") (pin "2") (pinfunction "2_2") (pintype "passive"))
      (node (ref "C6") (pin "1") (pinfunction "1_1") (pintype "passive"))
      (node (ref "C7") (pin "1") (pinfunction "1_1") (pintype "passive"))
      (node (ref "C9") (pin "2") (pinfunction "2_2") (pintype "passive"))
      (node (ref "D23") (pin "27") (pinfunction "DGND_27") (pintype "passive"))
      (node (ref "D23") (pin "3") (pinfunction "CPGND_3") (pintype "passive"))
      (node (ref "D23") (pin "9") (pinfunction "AGND_9") (pintype "passive"))
      (node (ref "D25") (pin "1") (pinfunction "MODSEL_1") (pintype "passive"))
      (node (ref "D25") (pin "13") (pinfunction "AM2_13") (pintype "passive"))
      (node (ref "D25") (pin "14") (pinfunction "AM1_14") (pintype "passive"))
      (node (ref "D25") (pin "15") (pinfunction "AM0_15") (pintype "passive"))
      (node (ref "D25") (pin "22") (pinfunction "GND_22") (pintype "passive"))
      (node (ref "D25") (pin "25") (pinfunction "GND_25") (pintype "passive"))
      (node (ref "D25") (pin "28") (pinfunction "GND_28") (pintype "passive"))
      (node (ref "D25") (pin "9") (pinfunction "GND_9") (pintype "passive"))
      (node (ref "R198") (pin "1") (pinfunction "1_1") (pintype "passive"))
      (node (ref "R200") (pin "2") (pinfunction "2_2") (pintype "passive"))
      (node (ref "R201") (pin "2") (pinfunction "2_2") (pintype "passive"))
      (node (ref "R204") (pin "1") (pinfunction "1_1") (pintype "passive"))
      (node (ref "R208") (pin "1") (pinfunction "1_1") (pintype "passive"))
      (node (ref "R212") (pin "1") (pinfunction "1_1") (pintype "passive"))
      (node (ref "R213") (pin "1") (pinfunction "1_1") (pintype "passive"))
      (node (ref "R214") (pin "1") (pinfunction "1_1") (pintype "passive"))
      (node (ref "R223") (pin "1") (pinfunction "1_1") (pintype "passive"))
      (node (ref "R229") (pin "1") (pinfunction "1_1") (pintype "passive"))
      (node (ref "VT26") (pin "2") (pinfunction "E_2") (pintype "passive"))
    )
    (net (code "24") (name "Net-(C371-Pad2)") (class "Default")
      (node (ref "C371") (pin "2") (pinfunction "2_2") (pintype "passive"))
      (node (ref "R216") (pin "2") (pinfunction "2_2") (pintype "passive"))
    )
    (net (code "25") (name "Net-(C372-Pad2)") (class "Default")
      (node (ref "C372") (pin "2") (pinfunction "2_2") (pintype "passive"))
      (node (ref "R215") (pin "2") (pinfunction "2_2") (pintype "passive"))
    )
    (net (code "26") (name "Net-(C377-Pad1)") (class "Default")
      (node (ref "C377") (pin "1") (pinfunction "1_1") (pintype "passive"))
      (node (ref "R221") (pin "1") (pinfunction "1_1") (pintype "passive"))
    )
    (net (code "27") (name "Net-(C378-Pad1)") (class "Default")
      (node (ref "C378") (pin "1") (pinfunction "1_1") (pintype "passive"))
      (node (ref "R219") (pin "1") (pinfunction "1_1") (pintype "passive"))
    )
    (net (code "28") (name "Net-(C390-Pad2)") (class "Default")
      (node (ref "C390") (pin "2") (pinfunction "2_2") (pintype "passive"))
      (node (ref "R226") (pin "2") (pinfunction "2_2") (pintype "passive"))
    )
    (net (code "29") (name "Net-(C391-Pad2)") (class "Default")
      (node (ref "C391") (pin "2") (pinfunction "2_2") (pintype "passive"))
      (node (ref "R224") (pin "2") (pinfunction "2_2") (pintype "passive"))
    )
    (net (code "30") (name "Net-(C396-Pad2)") (class "Default")
      (node (ref "C396") (pin "2") (pinfunction "2_2") (pintype "passive"))
      (node (ref "R227") (pin "1") (pinfunction "1_1") (pintype "passive"))
    )
    (net (code "31") (name "Net-(C397-Pad1)") (class "Default")
      (node (ref "C397") (pin "1") (pinfunction "1_1") (pintype "passive"))
      (node (ref "R231") (pin "1") (pinfunction "1_1") (pintype "passive"))
    )
    (net (code "32") (name "Net-(C398-Pad1)") (class "Default")
      (node (ref "C398") (pin "1") (pinfunction "1_1") (pintype "passive"))
      (node (ref "R230") (pin "1") (pinfunction "1_1") (pintype "passive"))
    )
    (net (code "33") (name "Net-(D23-CAPM)") (class "Default")
      (node (ref "C353") (pin "1") (pinfunction "1_1") (pintype "passive"))
      (node (ref "D23") (pin "4") (pinfunction "CAPM_4") (pintype "passive"))
    )
    (net (code "34") (name "Net-(D23-CAPP)") (class "Default")
      (node (ref "C353") (pin "2") (pinfunction "2_2") (pintype "passive"))
      (node (ref "D23") (pin "2") (pinfunction "CAPP_2") (pintype "passive"))
    )
    (net (code "35") (name "Net-(D23-DEMP)") (class "Default")
      (node (ref "D23") (pin "10") (pinfunction "DEMP_10") (pintype "passive"))
      (node (ref "R212") (pin "2") (pinfunction "2_2") (pintype "passive"))
    )
    (net (code "36") (name "Net-(D23-DOUT)") (class "Default")
      (node (ref "D23") (pin "16") (pinfunction "DOUT_16") (pintype "passive"))
      (node (ref "R194") (pin "1") (pinfunction "1_1") (pintype "passive"))
      (node (ref "R198") (pin "2") (pinfunction "2_2") (pintype "passive"))
    )
    (net (code "37") (name "Net-(D23-FLT)") (class "Default")
      (node (ref "D23") (pin "19") (pinfunction "FLT_19") (pintype "passive"))
      (node (ref "R213") (pin "2") (pinfunction "2_2") (pintype "passive"))
    )
    (net (code "38") (name "Net-(D23-FMT)") (class "Default")
      (node (ref "D23") (pin "24") (pinfunction "FMT_24") (pintype "passive"))
      (node (ref "R214") (pin "2") (pinfunction "2_2") (pintype "passive"))
    )
    (net (code "39") (name "Net-(D23-LDOO)") (class "Default")
      (node (ref "C367") (pin "2") (pinfunction "2_2") (pintype "passive"))
      (node (ref "D23") (pin "26") (pinfunction "LDOO_26") (pintype "passive"))
    )
    (net (code "40") (name "Net-(D23-MODE1)") (class "Default")
      (node (ref "D23") (pin "17") (pinfunction "MODE1_17") (pintype "passive"))
      (node (ref "R208") (pin "2") (pinfunction "2_2") (pintype "passive"))
    )
    (net (code "41") (name "Net-(D23-MODE2)") (class "Default")
      (node (ref "D23") (pin "18") (pinfunction "MODE2_18") (pintype "passive"))
      (node (ref "R211") (pin "2") (pinfunction "2_2") (pintype "passive"))
    )
    (net (code "42") (name "Net-(D23-OUTL)") (class "Default")
      (node (ref "D23") (pin "6") (pinfunction "OUTL_6") (pintype "passive"))
      (node (ref "R199") (pin "1") (pinfunction "1_1") (pintype "passive"))
    )
    (net (code "43") (name "Net-(D23-OUTR)") (class "Default")
      (node (ref "D23") (pin "7") (pinfunction "OUTR_7") (pintype "passive"))
      (node (ref "R197") (pin "1") (pinfunction "1_1") (pintype "passive"))
    )
    (net (code "44") (name "Net-(D23-SCK)") (class "Default")
      (node (ref "D23") (pin "20") (pinfunction "SCK_20") (pintype "passive"))
      (node (ref "R204") (pin "2") (pinfunction "2_2") (pintype "passive"))
      (node (ref "R206") (pin "2") (pinfunction "2_2") (pintype "passive"))
    )
    (net (code "45") (name "Net-(D23-VNEG)") (class "Default")
      (node (ref "C350") (pin "1") (pinfunction "1_1") (pintype "passive"))
      (node (ref "D23") (pin "5") (pinfunction "VNEG_5") (pintype "passive"))
    )
    (net (code "46") (name "Net-(D25-BSNL)") (class "Default")
      (node (ref "C388") (pin "1") (pinfunction "1_1") (pintype "passive"))
      (node (ref "D25") (pin "20") (pinfunction "BSNL_20") (pintype "passive"))
    )
    (net (code "47") (name "Net-(D25-BSNR)") (class "Default")
      (node (ref "C384") (pin "1") (pinfunction "1_1") (pintype "passive"))
      (node (ref "D25") (pin "26") (pinfunction "BSNR_26") (pintype "passive"))
    )
    (net (code "48") (name "Net-(D25-BSPL)") (class "Default")
      (node (ref "C385") (pin "1") (pinfunction "1_1") (pintype "passive"))
      (node (ref "D25") (pin "24") (pinfunction "BSPL_24") (pintype "passive"))
    )
    (net (code "49") (name "Net-(D25-BSPR)") (class "Default")
      (node (ref "C380") (pin "1") (pinfunction "1_1") (pintype "passive"))
      (node (ref "D25") (pin "30") (pinfunction "BSPR_30") (pintype "passive"))
    )
    (net (code "50") (name "Net-(D25-FAULTZ)") (class "Default")
      (node (ref "D25") (pin "3") (pinfunction "FAULTZ_3") (pintype "passive"))
      (node (ref "R220") (pin "2") (pinfunction "2_2") (pintype "passive"))
    )
    (net (code "51") (name "Net-(D25-GAIN{slash}SLV)") (class "Default")
      (node (ref "D25") (pin "8") (pinfunction "GAIN/SLV_8") (pintype "passive"))
      (node (ref "R222") (pin "2") (pinfunction "2_2") (pintype "passive"))
      (node (ref "R223") (pin "2") (pinfunction "2_2") (pintype "passive"))
    )
    (net (code "52") (name "Net-(D25-GVDD)") (class "Default")
      (node (ref "C383") (pin "1") (pinfunction "1_1") (pintype "passive"))
      (node (ref "D25") (pin "6") (pinfunction "PLIMIT_6") (pintype "passive"))
      (node (ref "D25") (pin "7") (pinfunction "GVDD_7") (pintype "passive"))
      (node (ref "R222") (pin "1") (pinfunction "1_1") (pintype "passive"))
    )
    (net (code "53") (name "Net-(D25-LINN)") (class "Default")
      (node (ref "C387") (pin "2") (pinfunction "2_2") (pintype "passive"))
      (node (ref "D25") (pin "11") (pinfunction "LINN_11") (pintype "passive"))
    )
    (net (code "54") (name "Net-(D25-LINP)") (class "Default")
      (node (ref "C386") (pin "2") (pinfunction "2_2") (pintype "passive"))
      (node (ref "D25") (pin "10") (pinfunction "LINP_10") (pintype "passive"))
    )
    (net (code "55") (name "Net-(D25-OUTNL)") (class "Default")
      (node (ref "C388") (pin "2") (pinfunction "2_2") (pintype "passive"))
      (node (ref "D25") (pin "21") (pinfunction "OUTNL_21") (pintype "passive"))
      (node (ref "L21") (pin "1") (pinfunction "1_1") (pintype "passive"))
      (node (ref "R231") (pin "2") (pinfunction "2_2") (pintype "passive"))
    )
    (net (code "56") (name "Net-(D25-OUTNR)") (class "Default")
      (node (ref "C384") (pin "2") (pinfunction "2_2") (pintype "passive"))
      (node (ref "D25") (pin "27") (pinfunction "OUTNR_27") (pintype "passive"))
      (node (ref "L19") (pin "1") (pinfunction "1_1") (pintype "passive"))
      (node (ref "R221") (pin "2") (pinfunction "2_2") (pintype "passive"))
    )
    (net (code "57") (name "Net-(D25-OUTPL)") (class "Default")
      (node (ref "C385") (pin "2") (pinfunction "2_2") (pintype "passive"))
      (node (ref "D25") (pin "23") (pinfunction "OUTPL_23") (pintype "passive"))
      (node (ref "L20") (pin "1") (pinfunction "1_1") (pintype "passive"))
      (node (ref "R226") (pin "1") (pinfunction "1_1") (pintype "passive"))
    )
    (net (code "58") (name "Net-(D25-OUTPR)") (class "Default")
      (node (ref "C380") (pin "2") (pinfunction "2_2") (pintype "passive"))
      (node (ref "D25") (pin "29") (pinfunction "OUTPR_29") (pintype "passive"))
      (node (ref "L18") (pin "1") (pinfunction "1_1") (pintype "passive"))
      (node (ref "R216") (pin "1") (pinfunction "1_1") (pintype "passive"))
    )
    (net (code "59") (name "Net-(D25-RINN)") (class "Default")
      (node (ref "C382") (pin "2") (pinfunction "2_2") (pintype "passive"))
      (node (ref "D25") (pin "5") (pinfunction "RINN_5") (pintype "passive"))
    )
    (net (code "60") (name "Net-(D25-RINP)") (class "Default")
      (node (ref "C381") (pin "2") (pinfunction "2_2") (pintype "passive"))
      (node (ref "D25") (pin "4") (pinfunction "RINP_4") (pintype "passive"))
    )
    (net (code "61") (name "Net-(D25-SYNC)") (class "Default")
      (node (ref "D25") (pin "16") (pinfunction "SYNC_16") (pintype "passive"))
      (node (ref "R227") (pin "2") (pinfunction "2_2") (pintype "passive"))
    )
    (net (code "62") (name "Net-(VT26-B)") (class "Default")
      (node (ref "R228") (pin "1") (pinfunction "1_1") (pintype "passive"))
      (node (ref "R229") (pin "2") (pinfunction "2_2") (pintype "passive"))
      (node (ref "VT26") (pin "1") (pinfunction "B_1") (pintype "passive"))
    )
    (net (code "63") (name "unconnected-(D23-AGNS-Pad15)") (class "Default")
      (node (ref "D23") (pin "15") (pinfunction "AGNS_15") (pintype "passive+no_connect"))
    )
    (net (code "64") (name "unconnected-(D23-ATT0-Pad13)") (class "Default")
      (node (ref "D23") (pin "13") (pinfunction "ATT0_13") (pintype "passive+no_connect"))
    )
    (net (code "65") (name "unconnected-(D23-MAST-Pad14)") (class "Default")
      (node (ref "D23") (pin "14") (pinfunction "MAST_14") (pintype "passive+no_connect"))
    )
    (net (code "66") (name "unconnected-(D23-XSMT-Pad25)") (class "Default")
      (node (ref "D23") (pin "25") (pinfunction "XSMT_25") (pintype "passive+no_connect"))
    )
  )
)
